# ProgrammateurFilPilote_1_0.net
KiCad netlist of a schematic drawn in EAGLE
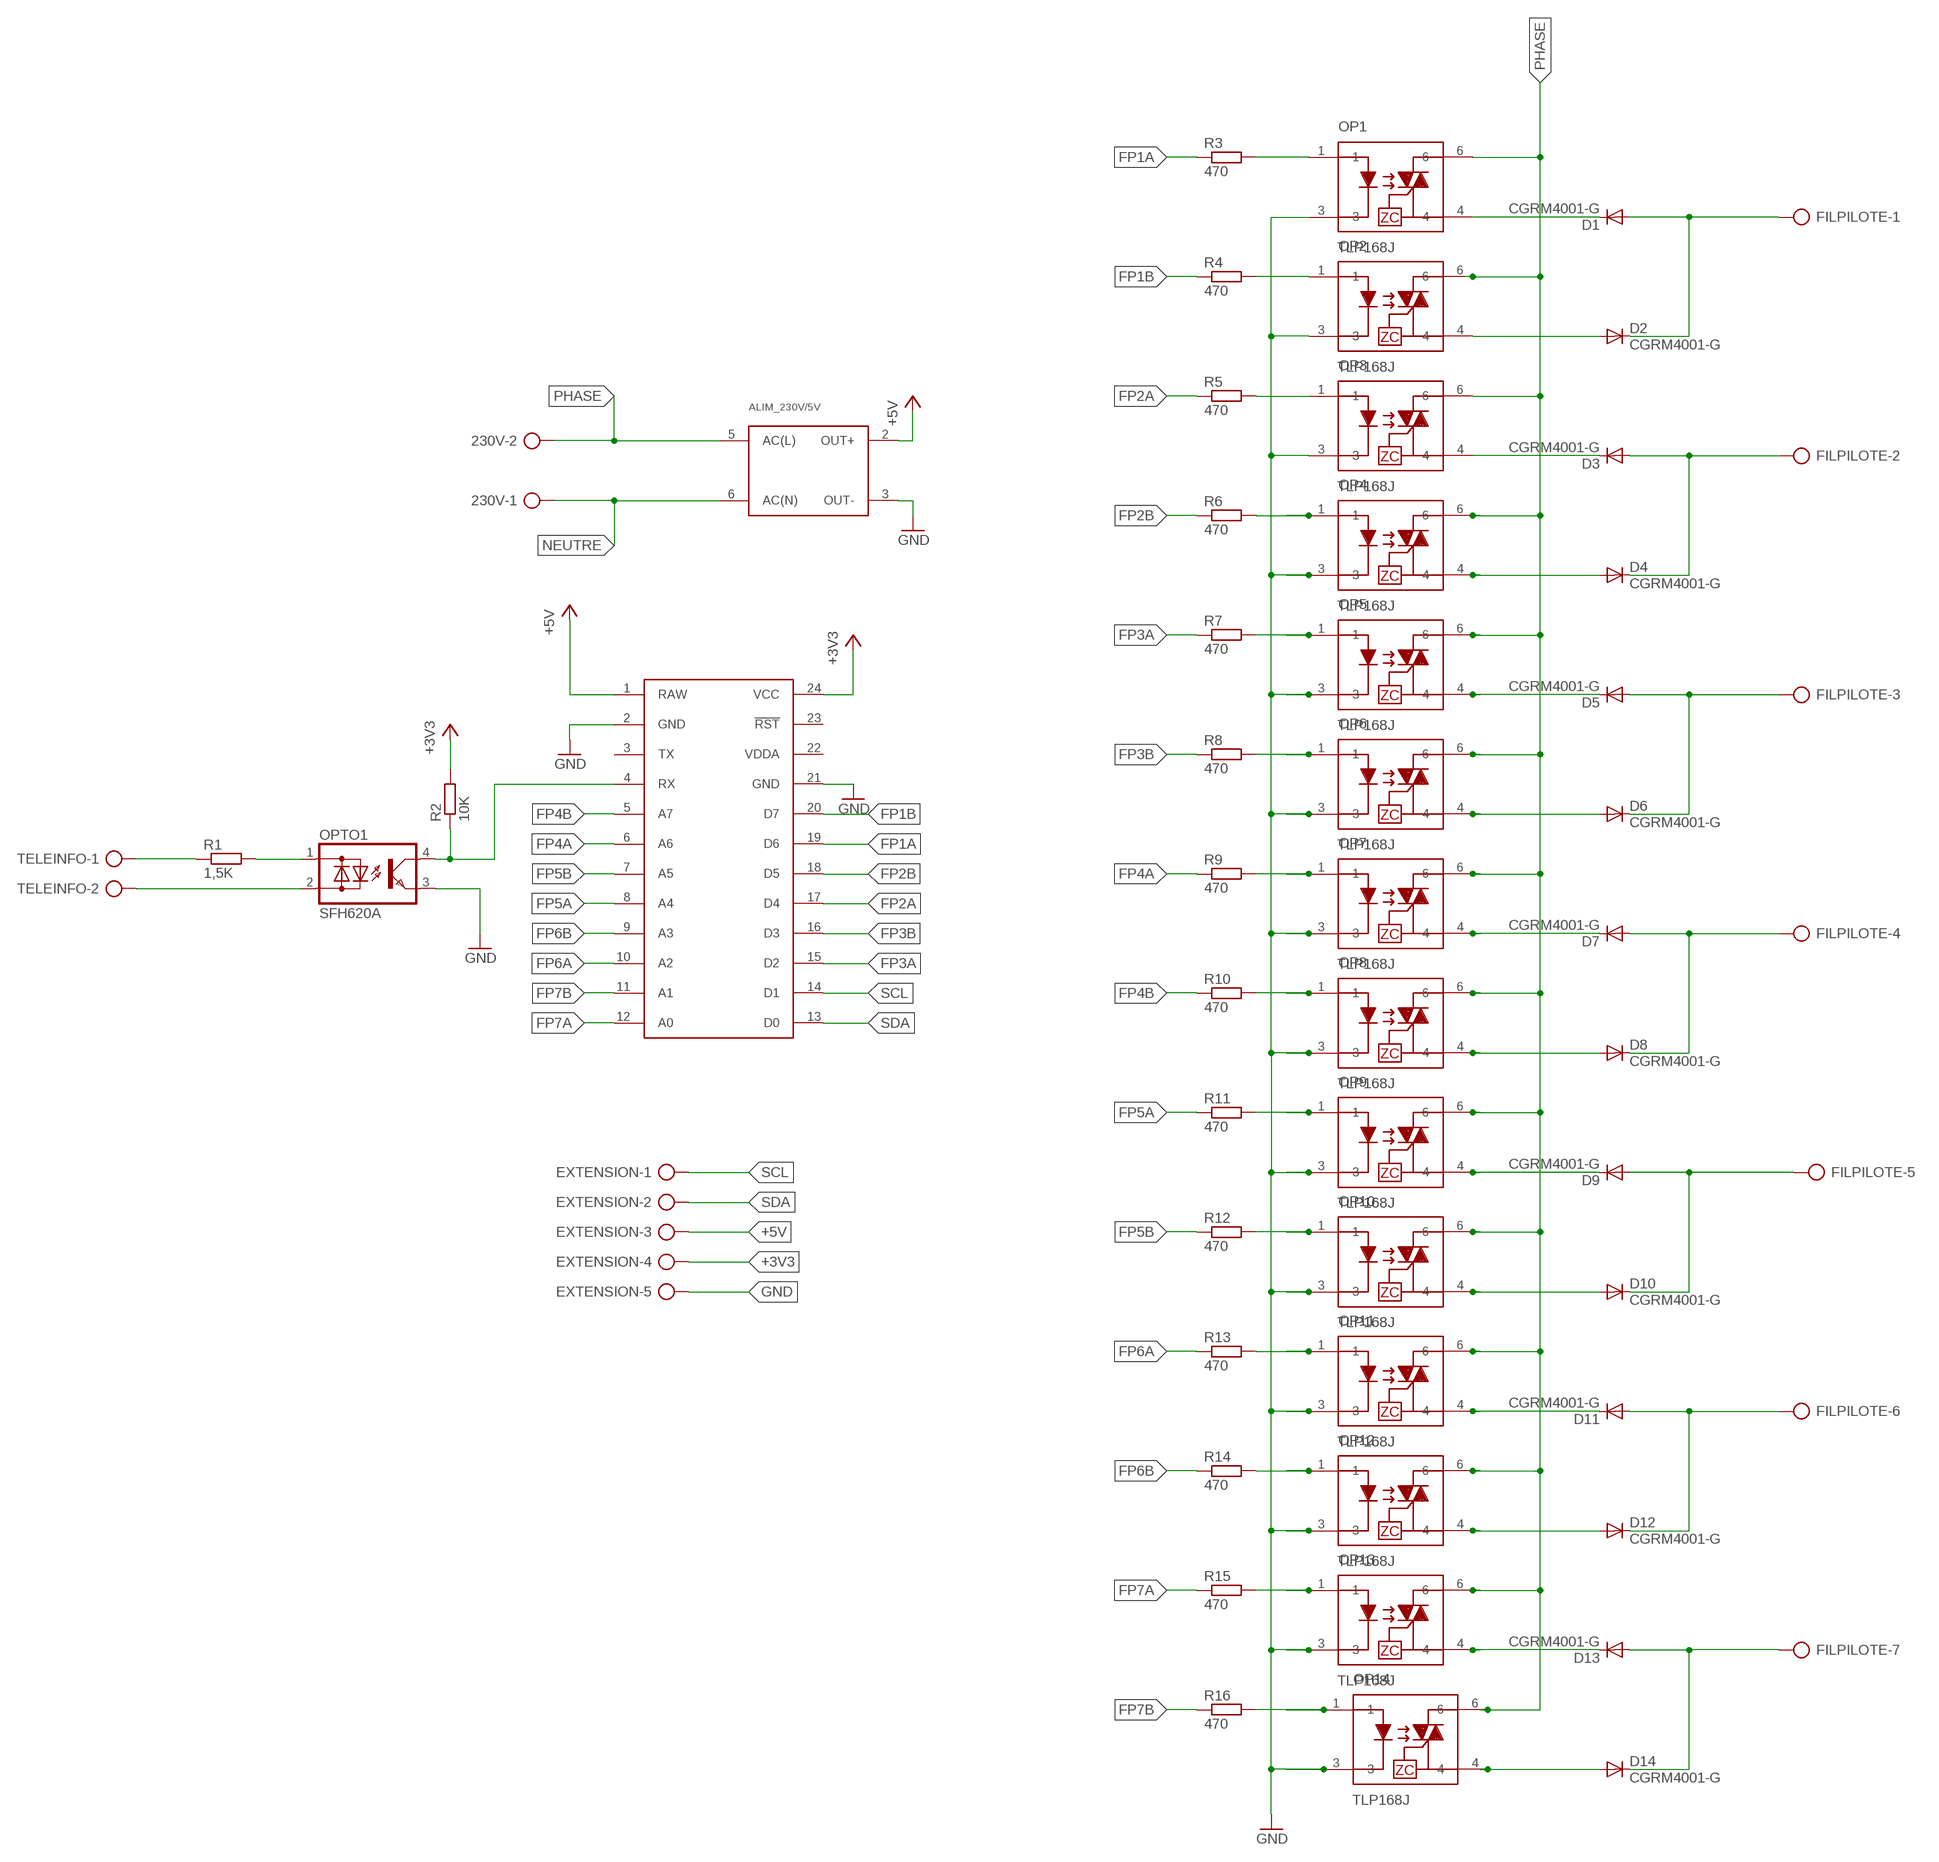
[diagram p0: schematic, sheet 1]

(export (version "E")
  (design (tool "Eeschema 10.0.6"))
  (components
    (comp (ref "230V")
      (value "AK500/2")
      (footprint "eagle-import:AK500_2")
      (libsource (lib "eagle-import") (part "AK500/2"))
    )
    (comp (ref "ALIM_230V/5V")
      (value "TMLM04-SINGLE")
      (footprint "eagle-import:TMLM04")
      (libsource (lib "eagle-import") (part "TMLM04-SINGLE"))
    )
    (comp (ref "D1")
      (value "CGRM4001-G")
      (footprint "eagle-import:SOD-123_MINI-SMA")
      (libsource (lib "eagle-import") (part "CGRM400-G1"))
    )
    (comp (ref "D2")
      (value "CGRM4001-G")
      (footprint "eagle-import:SOD-123_MINI-SMA")
      (libsource (lib "eagle-import") (part "CGRM400-G1"))
    )
    (comp (ref "D3")
      (value "CGRM4001-G")
      (footprint "eagle-import:SOD-123_MINI-SMA")
      (libsource (lib "eagle-import") (part "CGRM400-G1"))
    )
    (comp (ref "D4")
      (value "CGRM4001-G")
      (footprint "eagle-import:SOD-123_MINI-SMA")
      (libsource (lib "eagle-import") (part "CGRM400-G1"))
    )
    (comp (ref "D5")
      (value "CGRM4001-G")
      (footprint "eagle-import:SOD-123_MINI-SMA")
      (libsource (lib "eagle-import") (part "CGRM400-G1"))
    )
    (comp (ref "D6")
      (value "CGRM4001-G")
      (footprint "eagle-import:SOD-123_MINI-SMA")
      (libsource (lib "eagle-import") (part "CGRM400-G1"))
    )
    (comp (ref "D7")
      (value "CGRM4001-G")
      (footprint "eagle-import:SOD-123_MINI-SMA")
      (libsource (lib "eagle-import") (part "CGRM400-G1"))
    )
    (comp (ref "D8")
      (value "CGRM4001-G")
      (footprint "eagle-import:SOD-123_MINI-SMA")
      (libsource (lib "eagle-import") (part "CGRM400-G1"))
    )
    (comp (ref "D9")
      (value "CGRM4001-G")
      (footprint "eagle-import:SOD-123_MINI-SMA")
      (libsource (lib "eagle-import") (part "CGRM400-G1"))
    )
    (comp (ref "D10")
      (value "CGRM4001-G")
      (footprint "eagle-import:SOD-123_MINI-SMA")
      (libsource (lib "eagle-import") (part "CGRM400-G1"))
    )
    (comp (ref "D11")
      (value "CGRM4001-G")
      (footprint "eagle-import:SOD-123_MINI-SMA")
      (libsource (lib "eagle-import") (part "CGRM400-G1"))
    )
    (comp (ref "D12")
      (value "CGRM4001-G")
      (footprint "eagle-import:SOD-123_MINI-SMA")
      (libsource (lib "eagle-import") (part "CGRM400-G1"))
    )
    (comp (ref "D13")
      (value "CGRM4001-G")
      (footprint "eagle-import:SOD-123_MINI-SMA")
      (libsource (lib "eagle-import") (part "CGRM400-G1"))
    )
    (comp (ref "D14")
      (value "CGRM4001-G")
      (footprint "eagle-import:SOD-123_MINI-SMA")
      (libsource (lib "eagle-import") (part "CGRM400-G1"))
    )
    (comp (ref "EXTENSION")
      (value "AK500/5")
      (footprint "eagle-import:AK500_5")
      (libsource (lib "eagle-import") (part "AK500/5"))
    )
    (comp (ref "FILPILOTE")
      (value "AK500/7")
      (footprint "eagle-import:AK500_7")
      (libsource (lib "eagle-import") (part "AK500/7"))
    )
    (comp (ref "OP1")
      (value "TLP168J")
      (footprint "eagle-import:MFSOP-4")
      (libsource (lib "eagle-import") (part "TLP168J"))
    )
    (comp (ref "OP2")
      (value "TLP168J")
      (footprint "eagle-import:MFSOP-4")
      (libsource (lib "eagle-import") (part "TLP168J"))
    )
    (comp (ref "OP3")
      (value "TLP168J")
      (footprint "eagle-import:MFSOP-4")
      (libsource (lib "eagle-import") (part "TLP168J"))
    )
    (comp (ref "OP4")
      (value "TLP168J")
      (footprint "eagle-import:MFSOP-4")
      (libsource (lib "eagle-import") (part "TLP168J"))
    )
    (comp (ref "OP5")
      (value "TLP168J")
      (footprint "eagle-import:MFSOP-4")
      (libsource (lib "eagle-import") (part "TLP168J"))
    )
    (comp (ref "OP6")
      (value "TLP168J")
      (footprint "eagle-import:MFSOP-4")
      (libsource (lib "eagle-import") (part "TLP168J"))
    )
    (comp (ref "OP7")
      (value "TLP168J")
      (footprint "eagle-import:MFSOP-4")
      (libsource (lib "eagle-import") (part "TLP168J"))
    )
    (comp (ref "OP8")
      (value "TLP168J")
      (footprint "eagle-import:MFSOP-4")
      (libsource (lib "eagle-import") (part "TLP168J"))
    )
    (comp (ref "OP9")
      (value "TLP168J")
      (footprint "eagle-import:MFSOP-4")
      (libsource (lib "eagle-import") (part "TLP168J"))
    )
    (comp (ref "OP10")
      (value "TLP168J")
      (footprint "eagle-import:MFSOP-4")
      (libsource (lib "eagle-import") (part "TLP168J"))
    )
    (comp (ref "OP11")
      (value "TLP168J")
      (footprint "eagle-import:MFSOP-4")
      (libsource (lib "eagle-import") (part "TLP168J"))
    )
    (comp (ref "OP12")
      (value "TLP168J")
      (footprint "eagle-import:MFSOP-4")
      (libsource (lib "eagle-import") (part "TLP168J"))
    )
    (comp (ref "OP13")
      (value "TLP168J")
      (footprint "eagle-import:MFSOP-4")
      (libsource (lib "eagle-import") (part "TLP168J"))
    )
    (comp (ref "OP14")
      (value "TLP168J")
      (footprint "eagle-import:MFSOP-4")
      (libsource (lib "eagle-import") (part "TLP168J"))
    )
    (comp (ref "OPTO1")
      (value "SFH620A")
      (footprint "eagle-import:DIL04")
      (fields (field (name "MPN") "SFH620A-2"))
      (libsource (lib "eagle-import") (part "SFH620A"))
    )
    (comp (ref "R1")
      (value "1,5K")
      (footprint "eagle-import:R1206")
      (libsource (lib "eagle-import") (part "R-EU_R1206"))
    )
    (comp (ref "R2")
      (value "10K")
      (footprint "eagle-import:R1206")
      (libsource (lib "eagle-import") (part "R-EU_R1206"))
    )
    (comp (ref "R3")
      (value "470")
      (footprint "eagle-import:R1206")
      (libsource (lib "eagle-import") (part "R-EU_R1206"))
    )
    (comp (ref "R4")
      (value "470")
      (footprint "eagle-import:R1206")
      (libsource (lib "eagle-import") (part "R-EU_R1206"))
    )
    (comp (ref "R5")
      (value "470")
      (footprint "eagle-import:R1206")
      (libsource (lib "eagle-import") (part "R-EU_R1206"))
    )
    (comp (ref "R6")
      (value "470")
      (footprint "eagle-import:R1206")
      (libsource (lib "eagle-import") (part "R-EU_R1206"))
    )
    (comp (ref "R7")
      (value "470")
      (footprint "eagle-import:R1206")
      (libsource (lib "eagle-import") (part "R-EU_R1206"))
    )
    (comp (ref "R8")
      (value "470")
      (footprint "eagle-import:R1206")
      (libsource (lib "eagle-import") (part "R-EU_R1206"))
    )
    (comp (ref "R9")
      (value "470")
      (footprint "eagle-import:R1206")
      (libsource (lib "eagle-import") (part "R-EU_R1206"))
    )
    (comp (ref "R10")
      (value "470")
      (footprint "eagle-import:R1206")
      (libsource (lib "eagle-import") (part "R-EU_R1206"))
    )
    (comp (ref "R11")
      (value "470")
      (footprint "eagle-import:R1206")
      (libsource (lib "eagle-import") (part "R-EU_R1206"))
    )
    (comp (ref "R12")
      (value "470")
      (footprint "eagle-import:R1206")
      (libsource (lib "eagle-import") (part "R-EU_R1206"))
    )
    (comp (ref "R13")
      (value "470")
      (footprint "eagle-import:R1206")
      (libsource (lib "eagle-import") (part "R-EU_R1206"))
    )
    (comp (ref "R14")
      (value "470")
      (footprint "eagle-import:R1206")
      (libsource (lib "eagle-import") (part "R-EU_R1206"))
    )
    (comp (ref "R15")
      (value "470")
      (footprint "eagle-import:R1206")
      (libsource (lib "eagle-import") (part "R-EU_R1206"))
    )
    (comp (ref "R16")
      (value "470")
      (footprint "eagle-import:R1206")
      (libsource (lib "eagle-import") (part "R-EU_R1206"))
    )
    (comp (ref "SPARKCORE")
      (value "SPARK_CORECORE")
      (footprint "eagle-import:SPARK_CORE")
      (libsource (lib "eagle-import") (part "SPARK_CORECORE"))
    )
    (comp (ref "TELEINFO")
      (value "AK500/2")
      (footprint "eagle-import:AK500_2")
      (libsource (lib "eagle-import") (part "AK500/2"))
    )
  )
  (nets
    (net (code "1") (name "+3V3") (class "Default")
      (node (ref "EXTENSION") (pin "4") (pinfunction "KL_4") (pintype "passive"))
      (node (ref "R2") (pin "2") (pinfunction "2_2") (pintype "passive"))
      (node (ref "SPARKCORE") (pin "24") (pinfunction "VCC_24") (pintype "power_in"))
    )
    (net (code "2") (name "+5V") (class "Default")
      (node (ref "ALIM_230V/5V") (pin "2") (pinfunction "OUT+_2") (pintype "passive"))
      (node (ref "EXTENSION") (pin "3") (pinfunction "KL_3") (pintype "passive"))
      (node (ref "SPARKCORE") (pin "1") (pinfunction "RAW_1") (pintype "power_in"))
    )
    (net (code "3") (name "/VDDA") (class "Default")
      (node (ref "SPARKCORE") (pin "22") (pinfunction "VDDA_22") (pintype "power_in"))
    )
    (net (code "4") (name "FP1A") (class "Default")
      (node (ref "R3") (pin "1") (pinfunction "1_1") (pintype "passive"))
      (node (ref "SPARKCORE") (pin "19") (pinfunction "D6_19") (pintype "bidirectional"))
    )
    (net (code "5") (name "FP1B") (class "Default")
      (node (ref "R4") (pin "1") (pinfunction "1_1") (pintype "passive"))
      (node (ref "SPARKCORE") (pin "20") (pinfunction "D7_20") (pintype "bidirectional"))
    )
    (net (code "6") (name "FP2A") (class "Default")
      (node (ref "R5") (pin "1") (pinfunction "1_1") (pintype "passive"))
      (node (ref "SPARKCORE") (pin "17") (pinfunction "D4_17") (pintype "bidirectional"))
    )
    (net (code "7") (name "FP2B") (class "Default")
      (node (ref "R6") (pin "1") (pinfunction "1_1") (pintype "passive"))
      (node (ref "SPARKCORE") (pin "18") (pinfunction "D5_18") (pintype "bidirectional"))
    )
    (net (code "8") (name "FP3A") (class "Default")
      (node (ref "R7") (pin "1") (pinfunction "1_1") (pintype "passive"))
      (node (ref "SPARKCORE") (pin "15") (pinfunction "D2_15") (pintype "bidirectional"))
    )
    (net (code "9") (name "FP3B") (class "Default")
      (node (ref "R8") (pin "1") (pinfunction "1_1") (pintype "passive"))
      (node (ref "SPARKCORE") (pin "16") (pinfunction "D3_16") (pintype "bidirectional"))
    )
    (net (code "10") (name "FP4A") (class "Default")
      (node (ref "R9") (pin "1") (pinfunction "1_1") (pintype "passive"))
      (node (ref "SPARKCORE") (pin "6") (pinfunction "A6_6") (pintype "bidirectional"))
    )
    (net (code "11") (name "FP4B") (class "Default")
      (node (ref "R10") (pin "1") (pinfunction "1_1") (pintype "passive"))
      (node (ref "SPARKCORE") (pin "5") (pinfunction "A7_5") (pintype "bidirectional"))
    )
    (net (code "12") (name "FP5A") (class "Default")
      (node (ref "R11") (pin "1") (pinfunction "1_1") (pintype "passive"))
      (node (ref "SPARKCORE") (pin "8") (pinfunction "A4_8") (pintype "bidirectional"))
    )
    (net (code "13") (name "FP5B") (class "Default")
      (node (ref "R12") (pin "1") (pinfunction "1_1") (pintype "passive"))
      (node (ref "SPARKCORE") (pin "7") (pinfunction "A5_7") (pintype "bidirectional"))
    )
    (net (code "14") (name "FP6A") (class "Default")
      (node (ref "R13") (pin "1") (pinfunction "1_1") (pintype "passive"))
      (node (ref "SPARKCORE") (pin "10") (pinfunction "A2_10") (pintype "bidirectional"))
    )
    (net (code "15") (name "FP6B") (class "Default")
      (node (ref "R14") (pin "1") (pinfunction "1_1") (pintype "passive"))
      (node (ref "SPARKCORE") (pin "9") (pinfunction "A3_9") (pintype "bidirectional"))
    )
    (net (code "16") (name "FP7A") (class "Default")
      (node (ref "R15") (pin "1") (pinfunction "1_1") (pintype "passive"))
      (node (ref "SPARKCORE") (pin "12") (pinfunction "A0_12") (pintype "bidirectional"))
    )
    (net (code "17") (name "FP7B") (class "Default")
      (node (ref "R16") (pin "1") (pinfunction "1_1") (pintype "passive"))
      (node (ref "SPARKCORE") (pin "11") (pinfunction "A1_11") (pintype "bidirectional"))
    )
    (net (code "18") (name "GND") (class "Default")
      (node (ref "ALIM_230V/5V") (pin "3") (pinfunction "OUT-_3") (pintype "passive"))
      (node (ref "EXTENSION") (pin "5") (pinfunction "KL_5") (pintype "passive"))
      (node (ref "OP1") (pin "3") (pinfunction "3_3") (pintype "bidirectional"))
      (node (ref "OP10") (pin "3") (pinfunction "3_3") (pintype "bidirectional"))
      (node (ref "OP11") (pin "3") (pinfunction "3_3") (pintype "bidirectional"))
      (node (ref "OP12") (pin "3") (pinfunction "3_3") (pintype "bidirectional"))
      (node (ref "OP13") (pin "3") (pinfunction "3_3") (pintype "bidirectional"))
      (node (ref "OP14") (pin "3") (pinfunction "3_3") (pintype "bidirectional"))
      (node (ref "OP2") (pin "3") (pinfunction "3_3") (pintype "bidirectional"))
      (node (ref "OP3") (pin "3") (pinfunction "3_3") (pintype "bidirectional"))
      (node (ref "OP4") (pin "3") (pinfunction "3_3") (pintype "bidirectional"))
      (node (ref "OP5") (pin "3") (pinfunction "3_3") (pintype "bidirectional"))
      (node (ref "OP6") (pin "3") (pinfunction "3_3") (pintype "bidirectional"))
      (node (ref "OP7") (pin "3") (pinfunction "3_3") (pintype "bidirectional"))
      (node (ref "OP8") (pin "3") (pinfunction "3_3") (pintype "bidirectional"))
      (node (ref "OP9") (pin "3") (pinfunction "3_3") (pintype "bidirectional"))
      (node (ref "OPTO1") (pin "3") (pinfunction "E_3") (pintype "passive"))
      (node (ref "SPARKCORE") (pin "2") (pinfunction "GND_2") (pintype "power_in"))
      (node (ref "SPARKCORE") (pin "21") (pinfunction "GND_21") (pintype "power_in"))
    )
    (net (code "19") (name "NEUTRE") (class "Default")
      (node (ref "230V") (pin "1") (pinfunction "KL_1") (pintype "passive"))
      (node (ref "ALIM_230V/5V") (pin "6") (pinfunction "AC(N)_6") (pintype "input"))
    )
    (net (code "20") (name "Net-(D1-PadC)") (class "Default")
      (node (ref "D1") (pin "C") (pinfunction "C_C") (pintype "passive"))
      (node (ref "OP1") (pin "4") (pinfunction "4_4") (pintype "bidirectional"))
    )
    (net (code "21") (name "Net-(D2-PadA)") (class "Default")
      (node (ref "D2") (pin "A") (pinfunction "A_A") (pintype "passive"))
      (node (ref "OP2") (pin "4") (pinfunction "4_4") (pintype "bidirectional"))
    )
    (net (code "22") (name "Net-(D3-PadC)") (class "Default")
      (node (ref "D3") (pin "C") (pinfunction "C_C") (pintype "passive"))
      (node (ref "OP3") (pin "4") (pinfunction "4_4") (pintype "bidirectional"))
    )
    (net (code "23") (name "Net-(D4-PadA)") (class "Default")
      (node (ref "D4") (pin "A") (pinfunction "A_A") (pintype "passive"))
      (node (ref "OP4") (pin "4") (pinfunction "4_4") (pintype "bidirectional"))
    )
    (net (code "24") (name "Net-(D5-PadC)") (class "Default")
      (node (ref "D5") (pin "C") (pinfunction "C_C") (pintype "passive"))
      (node (ref "OP5") (pin "4") (pinfunction "4_4") (pintype "bidirectional"))
    )
    (net (code "25") (name "Net-(D6-PadA)") (class "Default")
      (node (ref "D6") (pin "A") (pinfunction "A_A") (pintype "passive"))
      (node (ref "OP6") (pin "4") (pinfunction "4_4") (pintype "bidirectional"))
    )
    (net (code "26") (name "Net-(D7-PadC)") (class "Default")
      (node (ref "D7") (pin "C") (pinfunction "C_C") (pintype "passive"))
      (node (ref "OP7") (pin "4") (pinfunction "4_4") (pintype "bidirectional"))
    )
    (net (code "27") (name "Net-(D8-PadA)") (class "Default")
      (node (ref "D8") (pin "A") (pinfunction "A_A") (pintype "passive"))
      (node (ref "OP8") (pin "4") (pinfunction "4_4") (pintype "bidirectional"))
    )
    (net (code "28") (name "Net-(D9-PadC)") (class "Default")
      (node (ref "D9") (pin "C") (pinfunction "C_C") (pintype "passive"))
      (node (ref "OP9") (pin "4") (pinfunction "4_4") (pintype "bidirectional"))
    )
    (net (code "29") (name "Net-(D10-PadA)") (class "Default")
      (node (ref "D10") (pin "A") (pinfunction "A_A") (pintype "passive"))
      (node (ref "OP10") (pin "4") (pinfunction "4_4") (pintype "bidirectional"))
    )
    (net (code "30") (name "Net-(D11-PadC)") (class "Default")
      (node (ref "D11") (pin "C") (pinfunction "C_C") (pintype "passive"))
      (node (ref "OP11") (pin "4") (pinfunction "4_4") (pintype "bidirectional"))
    )
    (net (code "31") (name "Net-(D12-PadA)") (class "Default")
      (node (ref "D12") (pin "A") (pinfunction "A_A") (pintype "passive"))
      (node (ref "OP12") (pin "4") (pinfunction "4_4") (pintype "bidirectional"))
    )
    (net (code "32") (name "Net-(D13-PadC)") (class "Default")
      (node (ref "D13") (pin "C") (pinfunction "C_C") (pintype "passive"))
      (node (ref "OP13") (pin "4") (pinfunction "4_4") (pintype "bidirectional"))
    )
    (net (code "33") (name "Net-(D14-PadA)") (class "Default")
      (node (ref "D14") (pin "A") (pinfunction "A_A") (pintype "passive"))
      (node (ref "OP14") (pin "4") (pinfunction "4_4") (pintype "bidirectional"))
    )
    (net (code "34") (name "Net-(FILPILOTEA-KL)") (class "Default")
      (node (ref "D1") (pin "A") (pinfunction "A_A") (pintype "passive"))
      (node (ref "D2") (pin "C") (pinfunction "C_C") (pintype "passive"))
      (node (ref "FILPILOTE") (pin "1") (pinfunction "KL_1") (pintype "passive"))
    )
    (net (code "35") (name "Net-(FILPILOTEB-KL)") (class "Default")
      (node (ref "D3") (pin "A") (pinfunction "A_A") (pintype "passive"))
      (node (ref "D4") (pin "C") (pinfunction "C_C") (pintype "passive"))
      (node (ref "FILPILOTE") (pin "2") (pinfunction "KL_2") (pintype "passive"))
    )
    (net (code "36") (name "Net-(FILPILOTEC-KL)") (class "Default")
      (node (ref "D5") (pin "A") (pinfunction "A_A") (pintype "passive"))
      (node (ref "D6") (pin "C") (pinfunction "C_C") (pintype "passive"))
      (node (ref "FILPILOTE") (pin "3") (pinfunction "KL_3") (pintype "passive"))
    )
    (net (code "37") (name "Net-(FILPILOTED-KL)") (class "Default")
      (node (ref "D7") (pin "A") (pinfunction "A_A") (pintype "passive"))
      (node (ref "D8") (pin "C") (pinfunction "C_C") (pintype "passive"))
      (node (ref "FILPILOTE") (pin "4") (pinfunction "KL_4") (pintype "passive"))
    )
    (net (code "38") (name "Net-(FILPILOTEE-KL)") (class "Default")
      (node (ref "D10") (pin "C") (pinfunction "C_C") (pintype "passive"))
      (node (ref "D9") (pin "A") (pinfunction "A_A") (pintype "passive"))
      (node (ref "FILPILOTE") (pin "5") (pinfunction "KL_5") (pintype "passive"))
    )
    (net (code "39") (name "Net-(FILPILOTEF-KL)") (class "Default")
      (node (ref "D11") (pin "A") (pinfunction "A_A") (pintype "passive"))
      (node (ref "D12") (pin "C") (pinfunction "C_C") (pintype "passive"))
      (node (ref "FILPILOTE") (pin "6") (pinfunction "KL_6") (pintype "passive"))
    )
    (net (code "40") (name "Net-(FILPILOTEG-KL)") (class "Default")
      (node (ref "D13") (pin "A") (pinfunction "A_A") (pintype "passive"))
      (node (ref "D14") (pin "C") (pinfunction "C_C") (pintype "passive"))
      (node (ref "FILPILOTE") (pin "7") (pinfunction "KL_7") (pintype "passive"))
    )
    (net (code "41") (name "Net-(OP1-Pad1)") (class "Default")
      (node (ref "OP1") (pin "1") (pinfunction "1_1") (pintype "bidirectional"))
      (node (ref "R3") (pin "2") (pinfunction "2_2") (pintype "passive"))
    )
    (net (code "42") (name "Net-(OP2-Pad1)") (class "Default")
      (node (ref "OP2") (pin "1") (pinfunction "1_1") (pintype "bidirectional"))
      (node (ref "R4") (pin "2") (pinfunction "2_2") (pintype "passive"))
    )
    (net (code "43") (name "Net-(OP3-Pad1)") (class "Default")
      (node (ref "OP3") (pin "1") (pinfunction "1_1") (pintype "bidirectional"))
      (node (ref "R5") (pin "2") (pinfunction "2_2") (pintype "passive"))
    )
    (net (code "44") (name "Net-(OP4-Pad1)") (class "Default")
      (node (ref "OP4") (pin "1") (pinfunction "1_1") (pintype "bidirectional"))
      (node (ref "R6") (pin "2") (pinfunction "2_2") (pintype "passive"))
    )
    (net (code "45") (name "Net-(OP5-Pad1)") (class "Default")
      (node (ref "OP5") (pin "1") (pinfunction "1_1") (pintype "bidirectional"))
      (node (ref "R7") (pin "2") (pinfunction "2_2") (pintype "passive"))
    )
    (net (code "46") (name "Net-(OP6-Pad1)") (class "Default")
      (node (ref "OP6") (pin "1") (pinfunction "1_1") (pintype "bidirectional"))
      (node (ref "R8") (pin "2") (pinfunction "2_2") (pintype "passive"))
    )
    (net (code "47") (name "Net-(OP7-Pad1)") (class "Default")
      (node (ref "OP7") (pin "1") (pinfunction "1_1") (pintype "bidirectional"))
      (node (ref "R9") (pin "2") (pinfunction "2_2") (pintype "passive"))
    )
    (net (code "48") (name "Net-(OP8-Pad1)") (class "Default")
      (node (ref "OP8") (pin "1") (pinfunction "1_1") (pintype "bidirectional"))
      (node (ref "R10") (pin "2") (pinfunction "2_2") (pintype "passive"))
    )
    (net (code "49") (name "Net-(OP9-Pad1)") (class "Default")
      (node (ref "OP9") (pin "1") (pinfunction "1_1") (pintype "bidirectional"))
      (node (ref "R11") (pin "2") (pinfunction "2_2") (pintype "passive"))
    )
    (net (code "50") (name "Net-(OP10-Pad1)") (class "Default")
      (node (ref "OP10") (pin "1") (pinfunction "1_1") (pintype "bidirectional"))
      (node (ref "R12") (pin "2") (pinfunction "2_2") (pintype "passive"))
    )
    (net (code "51") (name "Net-(OP11-Pad1)") (class "Default")
      (node (ref "OP11") (pin "1") (pinfunction "1_1") (pintype "bidirectional"))
      (node (ref "R13") (pin "2") (pinfunction "2_2") (pintype "passive"))
    )
    (net (code "52") (name "Net-(OP12-Pad1)") (class "Default")
      (node (ref "OP12") (pin "1") (pinfunction "1_1") (pintype "bidirectional"))
      (node (ref "R14") (pin "2") (pinfunction "2_2") (pintype "passive"))
    )
    (net (code "53") (name "Net-(OP13-Pad1)") (class "Default")
      (node (ref "OP13") (pin "1") (pinfunction "1_1") (pintype "bidirectional"))
      (node (ref "R15") (pin "2") (pinfunction "2_2") (pintype "passive"))
    )
    (net (code "54") (name "Net-(OP14-Pad1)") (class "Default")
      (node (ref "OP14") (pin "1") (pinfunction "1_1") (pintype "bidirectional"))
      (node (ref "R16") (pin "2") (pinfunction "2_2") (pintype "passive"))
    )
    (net (code "55") (name "Net-(OPTO1-AC1)") (class "Default")
      (node (ref "OPTO1") (pin "1") (pinfunction "AC1_1") (pintype "passive"))
      (node (ref "R1") (pin "2") (pinfunction "2_2") (pintype "passive"))
    )
    (net (code "56") (name "Net-(OPTO1-AC2)") (class "Default")
      (node (ref "OPTO1") (pin "2") (pinfunction "AC2_2") (pintype "passive"))
      (node (ref "TELEINFO") (pin "2") (pinfunction "KL_2") (pintype "passive"))
    )
    (net (code "57") (name "Net-(OPTO1-C)") (class "Default")
      (node (ref "OPTO1") (pin "4") (pinfunction "C_4") (pintype "passive"))
      (node (ref "R2") (pin "1") (pinfunction "1_1") (pintype "passive"))
      (node (ref "SPARKCORE") (pin "4") (pinfunction "RX_4") (pintype "bidirectional"))
    )
    (net (code "58") (name "Net-(TELEINFOA-KL)") (class "Default")
      (node (ref "R1") (pin "1") (pinfunction "1_1") (pintype "passive"))
      (node (ref "TELEINFO") (pin "1") (pinfunction "KL_1") (pintype "passive"))
    )
    (net (code "59") (name "PHASE") (class "Default")
      (node (ref "230V") (pin "2") (pinfunction "KL_2") (pintype "passive"))
      (node (ref "ALIM_230V/5V") (pin "5") (pinfunction "AC(L)_5") (pintype "input"))
      (node (ref "OP1") (pin "6") (pinfunction "6_6") (pintype "bidirectional"))
      (node (ref "OP10") (pin "6") (pinfunction "6_6") (pintype "bidirectional"))
      (node (ref "OP11") (pin "6") (pinfunction "6_6") (pintype "bidirectional"))
      (node (ref "OP12") (pin "6") (pinfunction "6_6") (pintype "bidirectional"))
      (node (ref "OP13") (pin "6") (pinfunction "6_6") (pintype "bidirectional"))
      (node (ref "OP14") (pin "6") (pinfunction "6_6") (pintype "bidirectional"))
      (node (ref "OP2") (pin "6") (pinfunction "6_6") (pintype "bidirectional"))
      (node (ref "OP3") (pin "6") (pinfunction "6_6") (pintype "bidirectional"))
      (node (ref "OP4") (pin "6") (pinfunction "6_6") (pintype "bidirectional"))
      (node (ref "OP5") (pin "6") (pinfunction "6_6") (pintype "bidirectional"))
      (node (ref "OP6") (pin "6") (pinfunction "6_6") (pintype "bidirectional"))
      (node (ref "OP7") (pin "6") (pinfunction "6_6") (pintype "bidirectional"))
      (node (ref "OP8") (pin "6") (pinfunction "6_6") (pintype "bidirectional"))
      (node (ref "OP9") (pin "6") (pinfunction "6_6") (pintype "bidirectional"))
    )
    (net (code "60") (name "SCL") (class "Default")
      (node (ref "EXTENSION") (pin "1") (pinfunction "KL_1") (pintype "passive"))
      (node (ref "SPARKCORE") (pin "14") (pinfunction "D1_14") (pintype "bidirectional"))
    )
    (net (code "61") (name "SDA") (class "Default")
      (node (ref "EXTENSION") (pin "2") (pinfunction "KL_2") (pintype "passive"))
      (node (ref "SPARKCORE") (pin "13") (pinfunction "D0_13") (pintype "bidirectional"))
    )
    (net (code "62") (name "unconnected-(SPARKCORE-TX-Pad3)") (class "Default")
      (node (ref "SPARKCORE") (pin "3") (pinfunction "TX_3") (pintype "bidirectional"))
    )
    (net (code "63") (name "unconnected-(SPARKCORE-~{RST}-Pad23)") (class "Default")
      (node (ref "SPARKCORE") (pin "23") (pinfunction "~{RST}_23") (pintype "bidirectional"))
    )
  )
)
